# Gimbal_IMU_Board.net
KiCad netlist of a schematic drawn in EAGLE
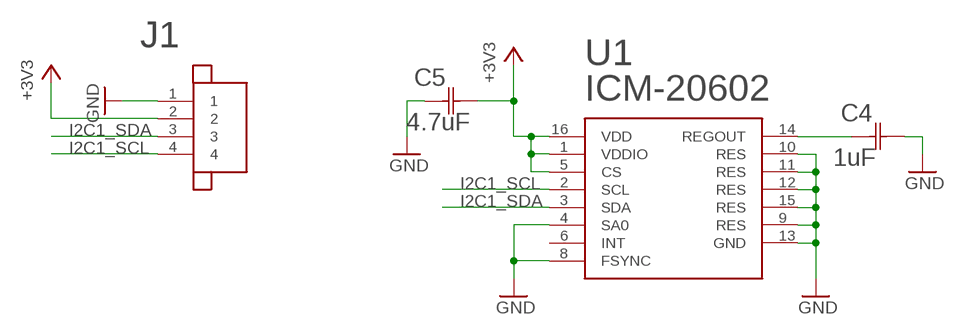
[diagram p0: schematic, sheet 1]

(export (version "E")
  (design (tool "Eeschema 10.0.6"))
  (components
    (comp (ref "C4")
      (value "1uF")
      (footprint "eagle-import:YAG_CC0805")
      (fields
        (field (name "MANUFACTURER_PART_NUMBER") "CC0805KKX7R7BB105")
        (field (name "COPYRIGHT") "Copyright C 2015 Accelerated Designs. All rights reserved")
      )
      (libsource (lib "eagle-import") (part "CC0805KKX7R7BB105"))
    )
    (comp (ref "C5")
      (value "4.7uF")
      (footprint "eagle-import:0603-M")
      (fields (field (name "MANUFACTURER_PART_NUMBER") "06036D475KAT2A"))
      (libsource (lib "eagle-import") (part "06036D475KAT2A0603-M"))
    )
    (comp (ref "J1")
      (value "JST_SH_4POS")
      (footprint "eagle-import:JST_SH_4POS")
      (libsource (lib "eagle-import") (part "JST_SH_4POS"))
    )
    (comp (ref "U1")
      (value "ICM-20602")
      (footprint "eagle-import:16LGA")
      (libsource (lib "eagle-import") (part "ICM-20602"))
    )
  )
  (nets
    (net (code "1") (name "+3V3") (class "Default")
      (node (ref "C5") (pin "2") (pinfunction "2_2") (pintype "passive"))
      (node (ref "J1") (pin "2") (pinfunction "2_2") (pintype "bidirectional"))
      (node (ref "U1") (pin "1") (pinfunction "VDDIO_1") (pintype "bidirectional"))
      (node (ref "U1") (pin "16") (pinfunction "VDD_16") (pintype "bidirectional"))
      (node (ref "U1") (pin "5") (pinfunction "CS_5") (pintype "bidirectional"))
    )
    (net (code "2") (name "/I2C1_SCL") (class "Default")
      (node (ref "J1") (pin "4") (pinfunction "4_4") (pintype "bidirectional"))
      (node (ref "U1") (pin "2") (pinfunction "SCL_2") (pintype "bidirectional"))
    )
    (net (code "3") (name "/I2C1_SDA") (class "Default")
      (node (ref "J1") (pin "3") (pinfunction "3_3") (pintype "bidirectional"))
      (node (ref "U1") (pin "3") (pinfunction "SDA_3") (pintype "bidirectional"))
    )
    (net (code "4") (name "GND") (class "Default")
      (node (ref "C4") (pin "2") (pinfunction "22_2") (pintype "passive"))
      (node (ref "C5") (pin "1") (pinfunction "1_1") (pintype "passive"))
      (node (ref "J1") (pin "1") (pinfunction "1_1") (pintype "bidirectional"))
      (node (ref "U1") (pin "10") (pinfunction "RES_10") (pintype "bidirectional"))
      (node (ref "U1") (pin "11") (pinfunction "RES_11") (pintype "bidirectional"))
      (node (ref "U1") (pin "12") (pinfunction "RES_12") (pintype "bidirectional"))
      (node (ref "U1") (pin "13") (pinfunction "GND_13") (pintype "bidirectional"))
      (node (ref "U1") (pin "15") (pinfunction "RES_15") (pintype "bidirectional"))
      (node (ref "U1") (pin "4") (pinfunction "SA0_4") (pintype "bidirectional"))
      (node (ref "U1") (pin "8") (pinfunction "FSYNC_8") (pintype "bidirectional"))
      (node (ref "U1") (pin "9") (pinfunction "RES_9") (pintype "bidirectional"))
    )
    (net (code "5") (name "Net-(C4-11)") (class "Default")
      (node (ref "C4") (pin "1") (pinfunction "11_1") (pintype "passive"))
      (node (ref "U1") (pin "14") (pinfunction "REGOUT_14") (pintype "bidirectional"))
    )
    (net (code "6") (name "unconnected-(U1-INT-Pad6)") (class "Default")
      (node (ref "U1") (pin "6") (pinfunction "INT_6") (pintype "bidirectional"))
    )
  )
)
